# OPTO_ISOLATION.net
KiCad netlist of a schematic drawn in Altium Designer
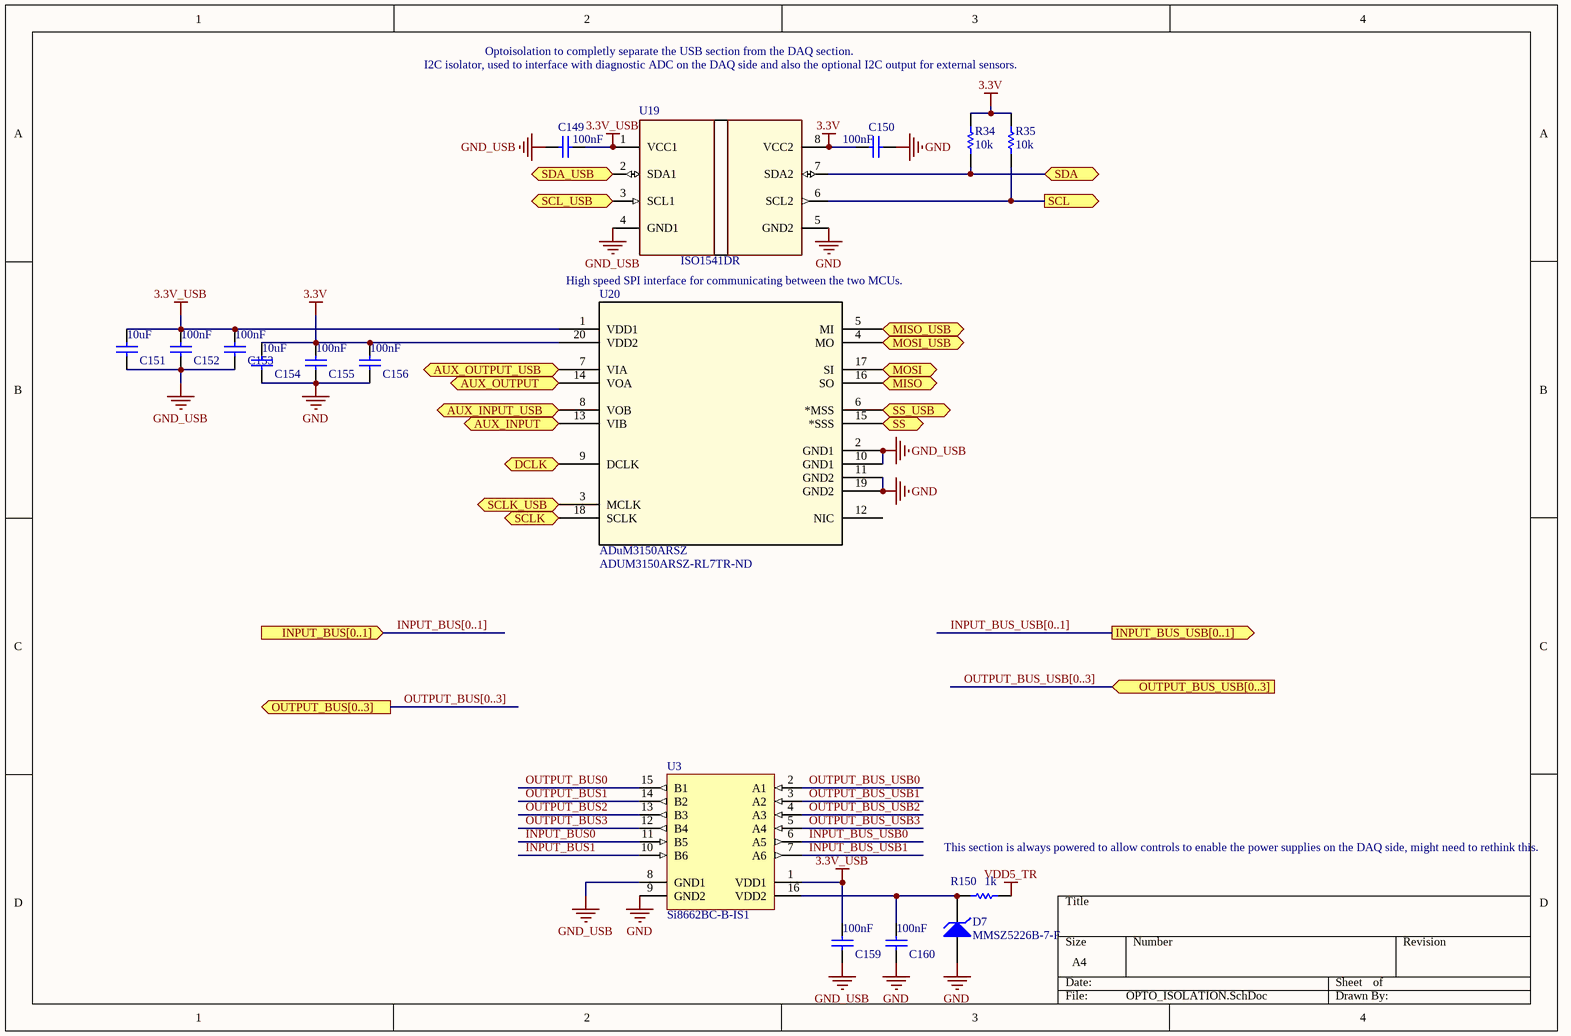
[diagram p0: OPTO_ISOLATION.SchDoc]

(export (version "E")
  (design (tool "Eeschema 10.0.6"))
  (components
    (comp (ref "C149")
      (value "100nF")
      (footprint "CAPC0402(1005)60_L")
      (description "0402 (1005 Metric) Chip Capacitor")
      (fields (field (name "Comment") "CAP0402"))
      (libsource (lib "Altium Content Vault") (part "CMP-1590-00004-1"))
    )
    (comp (ref "C150")
      (value "100nF")
      (footprint "CAPC0402(1005)60_L")
      (description "0402 (1005 Metric) Chip Capacitor")
      (fields (field (name "Comment") "CAP0402"))
      (libsource (lib "Altium Content Vault") (part "CMP-1590-00004-1"))
    )
    (comp (ref "C151")
      (value "10uF")
      (footprint "CAPC0805(2012)145_L")
      (description "0805 (2012 Metric) Chip Capacitor")
      (fields (field (name "Comment") "CAP0805"))
      (libsource (lib "Altium Content Vault") (part "CMP-1590-00003-1"))
    )
    (comp (ref "C152")
      (value "100nF")
      (footprint "CAPC0402(1005)60_L")
      (description "0402 (1005 Metric) Chip Capacitor")
      (fields (field (name "Comment") "CAP0402"))
      (libsource (lib "Altium Content Vault") (part "CMP-1590-00004-1"))
    )
    (comp (ref "C153")
      (value "100nF")
      (footprint "CAPC0402(1005)60_L")
      (description "0402 (1005 Metric) Chip Capacitor")
      (fields (field (name "Comment") "CAP0402"))
      (libsource (lib "Altium Content Vault") (part "CMP-1590-00004-1"))
    )
    (comp (ref "C154")
      (value "10uF")
      (footprint "CAPC0805(2012)145_L")
      (description "0805 (2012 Metric) Chip Capacitor")
      (fields (field (name "Comment") "CAP0805"))
      (libsource (lib "Altium Content Vault") (part "CMP-1590-00003-1"))
    )
    (comp (ref "C155")
      (value "100nF")
      (footprint "CAPC0402(1005)60_L")
      (description "0402 (1005 Metric) Chip Capacitor")
      (fields (field (name "Comment") "CAP0402"))
      (libsource (lib "Altium Content Vault") (part "CMP-1590-00004-1"))
    )
    (comp (ref "C156")
      (value "100nF")
      (footprint "CAPC0402(1005)60_L")
      (description "0402 (1005 Metric) Chip Capacitor")
      (fields (field (name "Comment") "CAP0402"))
      (libsource (lib "Altium Content Vault") (part "CMP-1590-00004-1"))
    )
    (comp (ref "C159")
      (value "100nF")
      (footprint "CAPC0402(1005)60_L")
      (description "0402 (1005 Metric) Chip Capacitor")
      (fields (field (name "Comment") "CAP0402"))
      (libsource (lib "Altium Content Vault") (part "CMP-1590-00004-1"))
    )
    (comp (ref "C160")
      (value "100nF")
      (footprint "CAPC0402(1005)60_L")
      (description "0402 (1005 Metric) Chip Capacitor")
      (fields (field (name "Comment") "CAP0402"))
      (libsource (lib "Altium Content Vault") (part "CMP-1590-00004-1"))
    )
    (comp (ref "D7")
      (value "MMSZ5226B-7-F")
      (footprint "DIOD-SOD-123-2-A_V")
      (description "Zener Diode, 500 mW, 3.3 V, -65 to 150 degC, 2-Pin SOD123, RoHS, Tape and Reel")
      (fields (field (name "MANUFACTURER") "DiodesIncorporated"))
      (libsource (lib "Altium Content Vault") (part "DZEN-AK-2"))
    )
    (comp (ref "R34")
      (value "10k")
      (footprint "RESC0402(1005)_L")
      (description "0402 (1005 Metric) Chip Resistor")
      (fields (field (name "Comment") "RES0402"))
      (libsource (lib "Altium Content Vault") (part "CMP-1591-00004-1"))
    )
    (comp (ref "R35")
      (value "10k")
      (footprint "RESC0402(1005)_L")
      (description "0402 (1005 Metric) Chip Resistor")
      (fields (field (name "Comment") "RES0402"))
      (libsource (lib "Altium Content Vault") (part "CMP-1591-00004-1"))
    )
    (comp (ref "R150")
      (value "1k")
      (footprint "RESC0603(1608)_L")
      (description "0603 (1608 Metric) Chip Resistor")
      (fields (field (name "Comment") "RES0603"))
      (libsource (lib "Altium Content Vault") (part "CMP-1591-00001-1"))
    )
    (comp (ref "U3")
      (value "Si8662BC-B-IS1")
      (footprint "SLAB-SOIC-16-NB_M")
      (fields (field (name "MANUFACTURER") "Silicon Labs"))
      (libsource (lib "Altium Content Vault") (part "SLAB-Si8X62XX-SOIC-16-WB-16"))
    )
    (comp (ref "U19")
      (value "ISO1541DR")
      (footprint "D0008A_N")
      (description "Imported")
      (fields
        (field (name "ALTERNATE_PARTNUMBER") "ISO1541D")
        (field (name "MANUFACTURER") "Texas Instruments")
      )
      (libsource (lib "DAQ_Replacement") (part "ISO1541DR"))
    )
    (comp (ref "U20")
      (value "ADuM3150ARSZ")
      (footprint "RS_20")
      (description "Imported")
      (fields
        (field (name "MANUFACTURER") "Analog Devices Inc.")
        (field (name "MANUFACTURER PART NUMBER") "ADUM3150ARSZ-RL7")
        (field (name "SUPPLIER PART NUMBER 1") "ADUM3150ARSZ-RL7TR-ND")
      )
      (libsource (lib "DAQ_Replacement") (part "ADuM3150ARSZ"))
    )
  )
  (nets
    (net (code "1") (name "/AUX_INPUT") (class "Default")
      (node (ref "U20") (pin "13") (pinfunction "VIB_13") (pintype "passive"))
    )
    (net (code "2") (name "/AUX_INPUT_USB") (class "Default")
      (node (ref "U20") (pin "8") (pinfunction "VOB_8") (pintype "passive"))
    )
    (net (code "3") (name "/AUX_OUTPUT") (class "Default")
      (node (ref "U20") (pin "14") (pinfunction "VOA_14") (pintype "passive"))
    )
    (net (code "4") (name "/AUX_OUTPUT_USB") (class "Default")
      (node (ref "U20") (pin "7") (pinfunction "VIA_7") (pintype "passive"))
    )
    (net (code "5") (name "/DCLK") (class "Default")
      (node (ref "U20") (pin "9") (pinfunction "DCLK_9") (pintype "passive"))
    )
    (net (code "6") (name "/INPUT_BUS0") (class "Default")
      (node (ref "U3") (pin "11") (pinfunction "B5_11") (pintype "input"))
    )
    (net (code "7") (name "/INPUT_BUS1") (class "Default")
      (node (ref "U3") (pin "10") (pinfunction "B6_10") (pintype "input"))
    )
    (net (code "9") (name "/INPUT_BUS_USB0") (class "Default")
      (node (ref "U3") (pin "6") (pinfunction "A5_6") (pintype "output"))
    )
    (net (code "10") (name "/INPUT_BUS_USB1") (class "Default")
      (node (ref "U3") (pin "7") (pinfunction "A6_7") (pintype "output"))
    )
    (net (code "12") (name "/MISO") (class "Default")
      (node (ref "U20") (pin "16") (pinfunction "SO_16") (pintype "passive"))
    )
    (net (code "13") (name "/MISO_USB") (class "Default")
      (node (ref "U20") (pin "5") (pinfunction "MI_5") (pintype "passive"))
    )
    (net (code "14") (name "/MOSI") (class "Default")
      (node (ref "U20") (pin "17") (pinfunction "SI_17") (pintype "passive"))
    )
    (net (code "15") (name "/MOSI_USB") (class "Default")
      (node (ref "U20") (pin "4") (pinfunction "MO_4") (pintype "passive"))
    )
    (net (code "16") (name "/OUTPUT_BUS0") (class "Default")
      (node (ref "U3") (pin "15") (pinfunction "B1_15") (pintype "output"))
    )
    (net (code "17") (name "/OUTPUT_BUS1") (class "Default")
      (node (ref "U3") (pin "14") (pinfunction "B2_14") (pintype "output"))
    )
    (net (code "18") (name "/OUTPUT_BUS2") (class "Default")
      (node (ref "U3") (pin "13") (pinfunction "B3_13") (pintype "output"))
    )
    (net (code "19") (name "/OUTPUT_BUS3") (class "Default")
      (node (ref "U3") (pin "12") (pinfunction "B4_12") (pintype "output"))
    )
    (net (code "21") (name "/OUTPUT_BUS_USB0") (class "Default")
      (node (ref "U3") (pin "2") (pinfunction "A1_2") (pintype "input"))
    )
    (net (code "22") (name "/OUTPUT_BUS_USB1") (class "Default")
      (node (ref "U3") (pin "3") (pinfunction "A2_3") (pintype "input"))
    )
    (net (code "23") (name "/OUTPUT_BUS_USB2") (class "Default")
      (node (ref "U3") (pin "4") (pinfunction "A3_4") (pintype "input"))
    )
    (net (code "24") (name "/OUTPUT_BUS_USB3") (class "Default")
      (node (ref "U3") (pin "5") (pinfunction "A4_5") (pintype "input"))
    )
    (net (code "26") (name "/SCL") (class "Default")
      (node (ref "R35") (pin "2") (pinfunction "2_2") (pintype "passive"))
      (node (ref "U19") (pin "6") (pinfunction "SCL2_6") (pintype "output"))
    )
    (net (code "27") (name "/SCLK") (class "Default")
      (node (ref "U20") (pin "18") (pinfunction "SCLK_18") (pintype "passive"))
    )
    (net (code "28") (name "/SCLK_USB") (class "Default")
      (node (ref "U20") (pin "3") (pinfunction "MCLK_3") (pintype "passive"))
    )
    (net (code "29") (name "/SCL_USB") (class "Default")
      (node (ref "U19") (pin "3") (pinfunction "SCL1_3") (pintype "input"))
    )
    (net (code "30") (name "/SDA") (class "Default")
      (node (ref "R34") (pin "2") (pinfunction "2_2") (pintype "passive"))
      (node (ref "U19") (pin "7") (pinfunction "SDA2_7") (pintype "bidirectional"))
    )
    (net (code "31") (name "/SDA_USB") (class "Default")
      (node (ref "U19") (pin "2") (pinfunction "SDA1_2") (pintype "bidirectional"))
    )
    (net (code "32") (name "/SS") (class "Default")
      (node (ref "U20") (pin "15") (pinfunction "*SSS_15") (pintype "passive"))
    )
    (net (code "33") (name "/SS_USB") (class "Default")
      (node (ref "U20") (pin "6") (pinfunction "*MSS_6") (pintype "passive"))
    )
    (net (code "34") (name "3.3V") (class "Default")
      (node (ref "C150") (pin "1") (pinfunction "1_1") (pintype "passive"))
      (node (ref "C154") (pin "2") (pinfunction "2_2") (pintype "passive"))
      (node (ref "C155") (pin "1") (pinfunction "1_1") (pintype "passive"))
      (node (ref "C156") (pin "1") (pinfunction "1_1") (pintype "passive"))
      (node (ref "R34") (pin "1") (pinfunction "1_1") (pintype "passive"))
      (node (ref "R35") (pin "1") (pinfunction "1_1") (pintype "passive"))
      (node (ref "U19") (pin "8") (pinfunction "VCC2_8") (pintype "power_in"))
      (node (ref "U20") (pin "20") (pinfunction "VDD2_20") (pintype "passive"))
    )
    (net (code "35") (name "3.3V_USB") (class "Default")
      (node (ref "C149") (pin "2") (pinfunction "2_2") (pintype "passive"))
      (node (ref "C151") (pin "2") (pinfunction "2_2") (pintype "passive"))
      (node (ref "C152") (pin "1") (pinfunction "1_1") (pintype "passive"))
      (node (ref "C153") (pin "1") (pinfunction "1_1") (pintype "passive"))
      (node (ref "C159") (pin "1") (pinfunction "1_1") (pintype "passive"))
      (node (ref "U19") (pin "1") (pinfunction "VCC1_1") (pintype "power_in"))
      (node (ref "U20") (pin "1") (pinfunction "VDD1_1") (pintype "passive"))
      (node (ref "U3") (pin "1") (pinfunction "VDD1_1") (pintype "power_in"))
    )
    (net (code "36") (name "GND") (class "Default")
      (node (ref "C150") (pin "2") (pinfunction "2_2") (pintype "passive"))
      (node (ref "C154") (pin "1") (pinfunction "1_1") (pintype "passive"))
      (node (ref "C155") (pin "2") (pinfunction "2_2") (pintype "passive"))
      (node (ref "C156") (pin "2") (pinfunction "2_2") (pintype "passive"))
      (node (ref "C160") (pin "2") (pinfunction "2_2") (pintype "passive"))
      (node (ref "D7") (pin "1") (pinfunction "A_1") (pintype "passive"))
      (node (ref "U19") (pin "5") (pinfunction "GND2_5") (pintype "power_in"))
      (node (ref "U20") (pin "11") (pinfunction "GND2_11") (pintype "passive"))
      (node (ref "U20") (pin "19") (pinfunction "GND2_19") (pintype "passive"))
      (node (ref "U3") (pin "9") (pinfunction "GND2_9") (pintype "power_in"))
    )
    (net (code "37") (name "GND_USB") (class "Default")
      (node (ref "C149") (pin "1") (pinfunction "1_1") (pintype "passive"))
      (node (ref "C151") (pin "1") (pinfunction "1_1") (pintype "passive"))
      (node (ref "C152") (pin "2") (pinfunction "2_2") (pintype "passive"))
      (node (ref "C153") (pin "2") (pinfunction "2_2") (pintype "passive"))
      (node (ref "C159") (pin "2") (pinfunction "2_2") (pintype "passive"))
      (node (ref "U19") (pin "4") (pinfunction "GND1_4") (pintype "power_in"))
      (node (ref "U20") (pin "10") (pinfunction "GND1_10") (pintype "passive"))
      (node (ref "U20") (pin "2") (pinfunction "GND1_2") (pintype "passive"))
      (node (ref "U3") (pin "8") (pinfunction "GND1_8") (pintype "power_in"))
    )
    (net (code "38") (name "Net-(D7-K)") (class "Default")
      (node (ref "C160") (pin "1") (pinfunction "1_1") (pintype "passive"))
      (node (ref "D7") (pin "2") (pinfunction "K_2") (pintype "passive"))
      (node (ref "R150") (pin "1") (pinfunction "1_1") (pintype "passive"))
      (node (ref "U3") (pin "16") (pinfunction "VDD2_16") (pintype "power_in"))
    )
    (net (code "39") (name "VDD5_TR") (class "Default")
      (node (ref "R150") (pin "2") (pinfunction "2_2") (pintype "passive"))
    )
    (net (code "40") (name "unconnected-(U20-NIC-Pad12)") (class "Default")
      (node (ref "U20") (pin "12") (pinfunction "NIC_12") (pintype "passive"))
    )
  )
)
